# Main_Board.net
KiCad netlist of a schematic drawn in Altium Designer
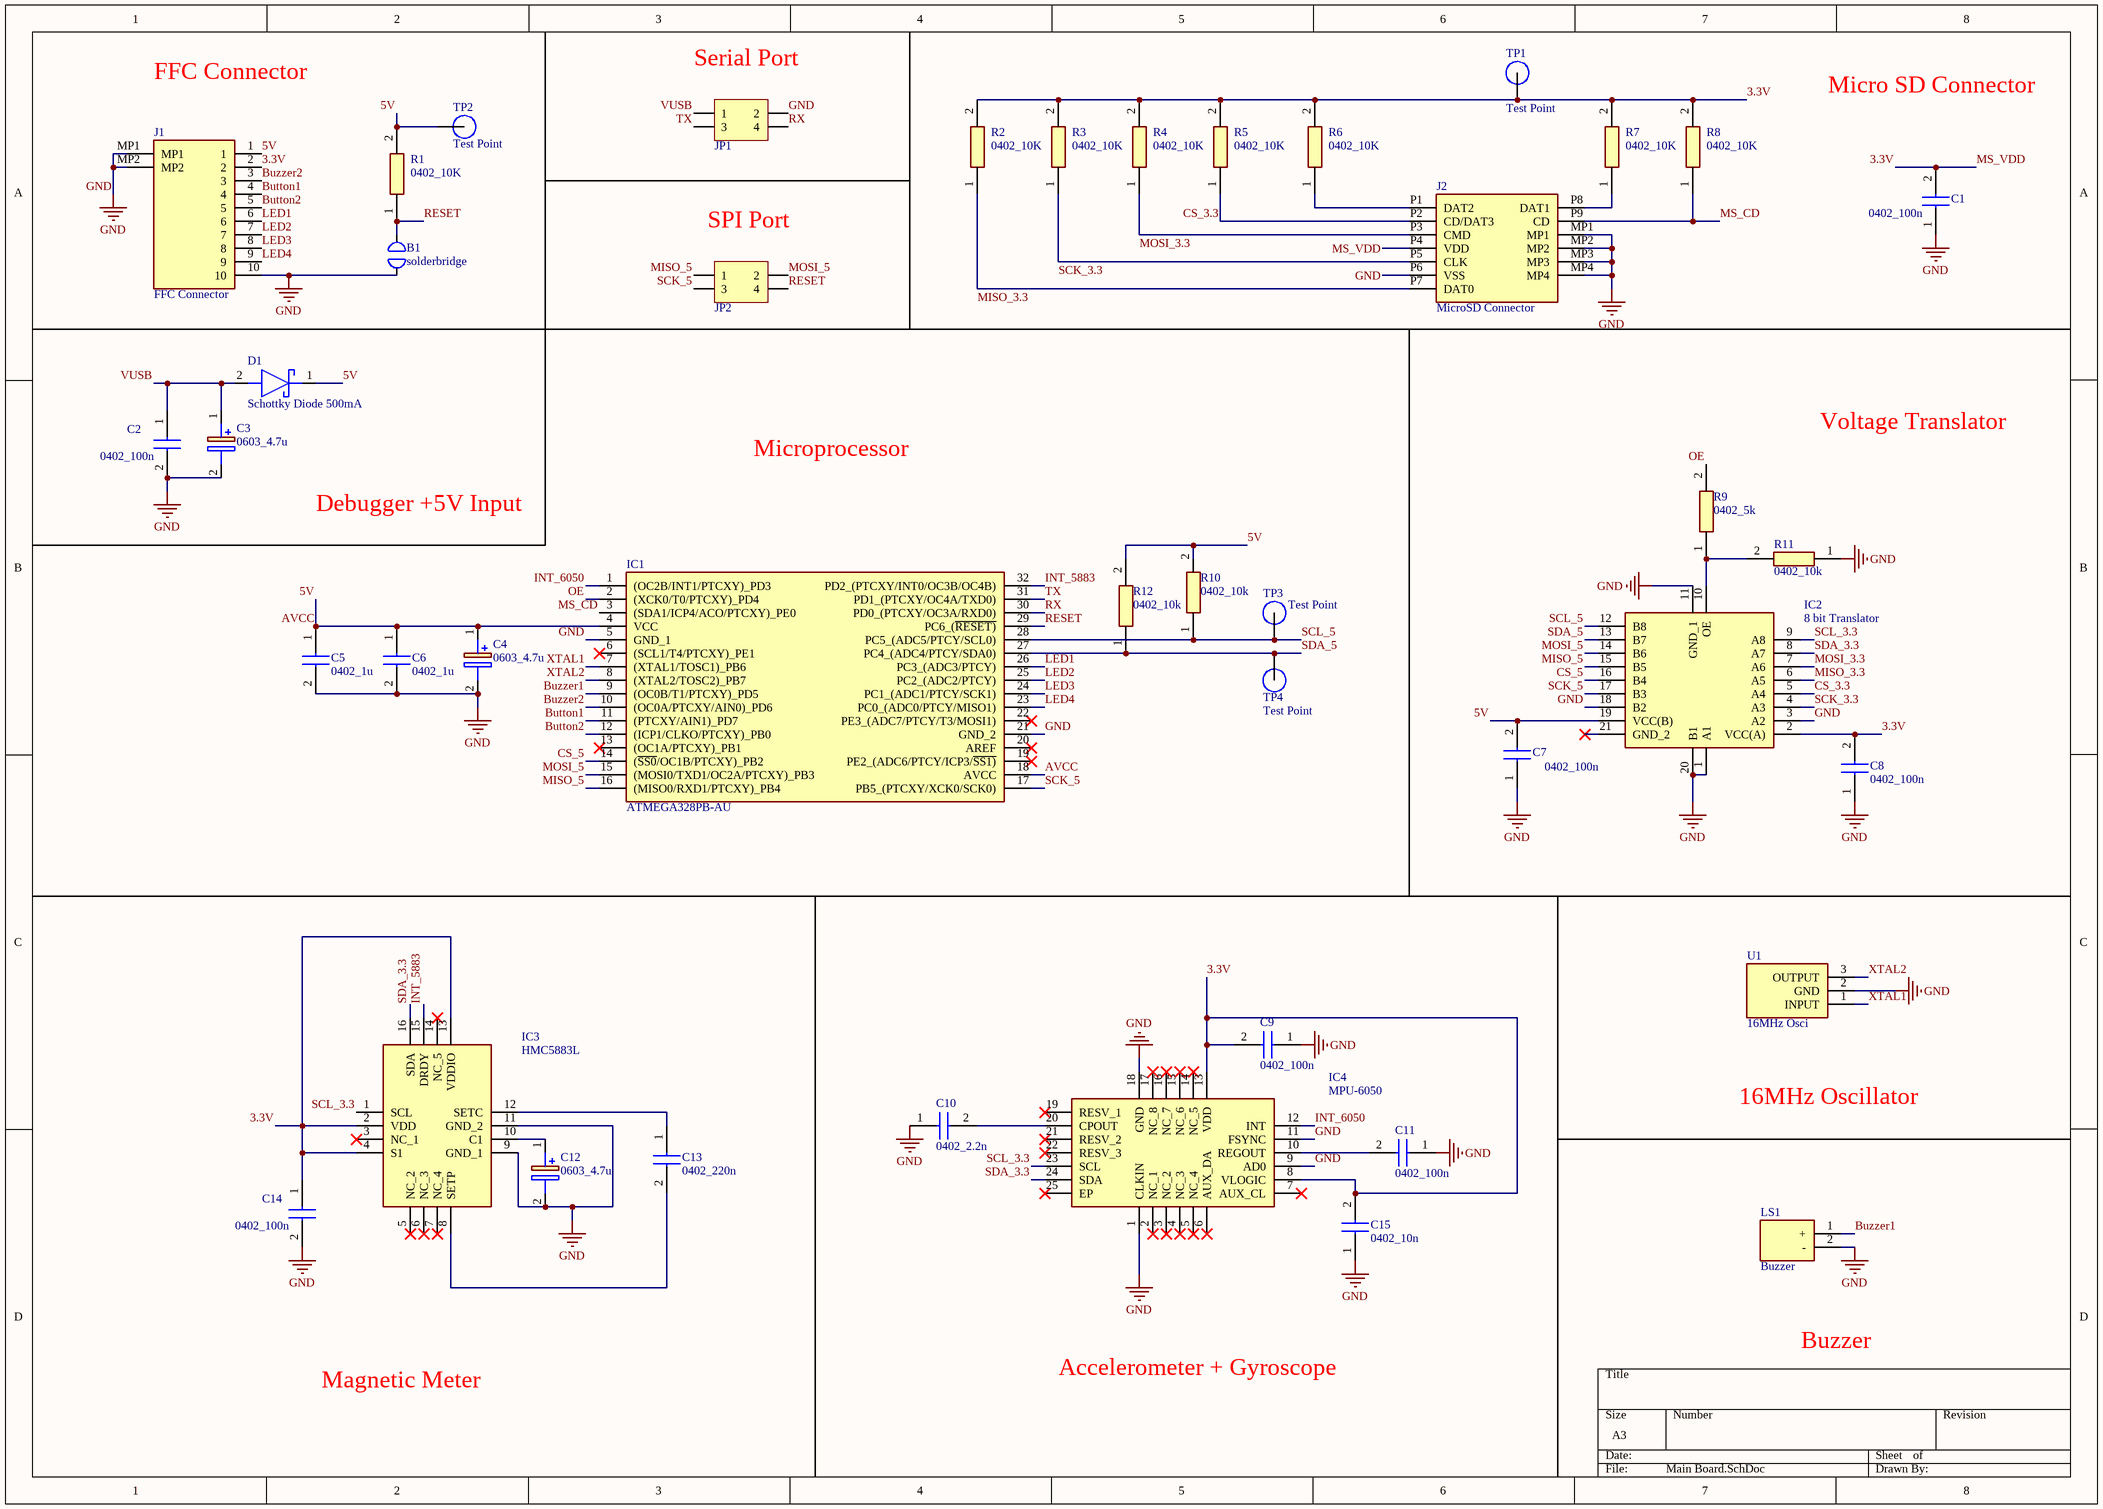
[diagram p0: Main Board.SchDoc]

(export (version "E")
  (design (tool "Eeschema 10.0.6"))
  (components
    (comp (ref "B1")
      (value "solderbridge")
      (footprint "Solderbridge")
      (libsource (lib "Main Board SCH Lib") (part "solderbridge"))
    )
    (comp (ref "C1")
      (value "0402_100n")
      (footprint "Main Board PCB Lib:CAPC1005X55N")
      (description "Capacitor")
      (fields (field (name "MANUFACTURER_PART_NUMBER") "VJ0603HIFRQ1KIT"))
      (libsource (lib "Main Board SCH Lib") (part "0603_C"))
    )
    (comp (ref "C2")
      (value "0402_100n")
      (footprint "CAPC1005X55N")
      (description "Capacitor")
      (fields (field (name "MANUFACTURER_PART_NUMBER") "VJ0603HIFRQ1KIT"))
      (libsource (lib "Main Board SCH Lib") (part "0603_C"))
    )
    (comp (ref "C3")
      (value "0603_4.7u")
      (footprint "SamacSys:CAPPM168X90N")
      (description "Capacitor Polarised")
      (fields (field (name "MANUFACTURER_PART_NUMBER") "TMCJ0J475MTRF"))
      (libsource (lib "Main Board SCH Lib") (part "0603_Tan"))
    )
    (comp (ref "C4")
      (value "0603_4.7u")
      (footprint "SamacSys:CAPPM168X90N")
      (description "Capacitor Polarised")
      (fields (field (name "MANUFACTURER_PART_NUMBER") "TMCJ0J475MTRF"))
      (libsource (lib "Main Board SCH Lib") (part "0603_Tan"))
    )
    (comp (ref "C5")
      (value "0402_1u")
      (footprint "Main Board PCB Lib:CAPC1005X55N")
      (description "Capacitor")
      (fields (field (name "MANUFACTURER_PART_NUMBER") "VJ0603HIFRQ1KIT"))
      (libsource (lib "Main Board SCH Lib") (part "0603_C"))
    )
    (comp (ref "C6")
      (value "0402_1u")
      (footprint "Main Board PCB Lib:CAPC1005X55N")
      (description "Capacitor")
      (fields (field (name "MANUFACTURER_PART_NUMBER") "VJ0603HIFRQ1KIT"))
      (libsource (lib "Main Board SCH Lib") (part "0603_C"))
    )
    (comp (ref "C7")
      (value "0402_100n")
      (footprint "Main Board PCB Lib:CAPC1005X55N")
      (description "Capacitor")
      (fields (field (name "MANUFACTURER_PART_NUMBER") "VJ0603HIFRQ1KIT"))
      (libsource (lib "Main Board SCH Lib") (part "0603_C"))
    )
    (comp (ref "C8")
      (value "0402_100n")
      (footprint "Main Board PCB Lib:CAPC1005X55N")
      (description "Capacitor")
      (fields (field (name "MANUFACTURER_PART_NUMBER") "VJ0603HIFRQ1KIT"))
      (libsource (lib "Main Board SCH Lib") (part "0603_C"))
    )
    (comp (ref "C9")
      (value "0402_100n")
      (footprint "Main Board PCB Lib:CAPC1005X55N")
      (description "Capacitor")
      (fields (field (name "MANUFACTURER_PART_NUMBER") "VJ0603HIFRQ1KIT"))
      (libsource (lib "Main Board SCH Lib") (part "0603_C"))
    )
    (comp (ref "C10")
      (value "0402_2.2n")
      (footprint "Main Board PCB Lib:CAPC1005X55N")
      (description "Capacitor")
      (fields (field (name "MANUFACTURER_PART_NUMBER") "VJ0603HIFRQ1KIT"))
      (libsource (lib "Main Board SCH Lib") (part "0603_C"))
    )
    (comp (ref "C11")
      (value "0402_100n")
      (footprint "Main Board PCB Lib:CAPC1005X55N")
      (description "Capacitor")
      (fields (field (name "MANUFACTURER_PART_NUMBER") "VJ0603HIFRQ1KIT"))
      (libsource (lib "Main Board SCH Lib") (part "0603_C"))
    )
    (comp (ref "C12")
      (value "0603_4.7u")
      (footprint "SamacSys:CAPPM168X90N")
      (description "Capacitor Polarised")
      (fields (field (name "MANUFACTURER_PART_NUMBER") "TMCJ0J475MTRF"))
      (libsource (lib "Main Board SCH Lib") (part "0603_Tan"))
    )
    (comp (ref "C13")
      (value "0402_220n")
      (footprint "Main Board PCB Lib:CAPC1005X55N")
      (description "Capacitor")
      (fields (field (name "MANUFACTURER_PART_NUMBER") "VJ0603HIFRQ1KIT"))
      (libsource (lib "Main Board SCH Lib") (part "0603_C"))
    )
    (comp (ref "C14")
      (value "0402_100n")
      (footprint "Main Board PCB Lib:CAPC1005X55N")
      (description "Capacitor")
      (fields (field (name "MANUFACTURER_PART_NUMBER") "VJ0603HIFRQ1KIT"))
      (libsource (lib "Main Board SCH Lib") (part "0603_C"))
    )
    (comp (ref "C15")
      (value "0402_10n")
      (footprint "Main Board PCB Lib:CAPC1005X55N")
      (description "Capacitor")
      (fields (field (name "MANUFACTURER_PART_NUMBER") "VJ0603HIFRQ1KIT"))
      (libsource (lib "Main Board SCH Lib") (part "0603_C"))
    )
    (comp (ref "D1")
      (value "Schottky Diode 500mA")
      (footprint "SamacSys:DIOC1709X85N")
      (description "Schottky Diode")
      (fields
        (field (name "MOUSER2 PART NUMBER") "750-CDBU0520")
        (field (name "MANUFACTURER_PART_NUMBER") "CDBU0520")
      )
      (libsource (lib "Main Board SCH Lib") (part "Schottky Diode 500mA"))
    )
    (comp (ref "IC1")
      (value "ATMEGA328PB-AU")
      (footprint "SamacSys:QFP80P900X900X120-32N")
      (description "Integrated Circuit")
      (fields (field (name "MOUSER2 PART NUMBER") "556-ATMEGA328PB-AU"))
      (libsource (lib "Main Board SCH Lib") (part "ATMEGA328PB-AU"))
    )
    (comp (ref "IC2")
      (value "8 bit Translator")
      (footprint "SamacSys:NXB0108BQX")
      (description "Integrated Circuit")
      (fields (field (name "MANUFACTURER_PART_NUMBER") "NXB0108BQX"))
      (libsource (lib "Main Board SCH Lib") (part "8 bit Translator"))
    )
    (comp (ref "IC3")
      (value "HMC5883L")
      (footprint "SamacSys:HMC5883L")
      (description "Integrated Circuit")
      (libsource (lib "Main Board SCH Lib") (part "HMC5883L"))
    )
    (comp (ref "IC4")
      (value "MPU-6050")
      (footprint "MPU_6050")
      (description "Integrated Circuit")
      (libsource (lib "Main Board SCH Lib") (part "MPU-6050"))
    )
    (comp (ref "J1")
      (value "FFC Connector")
      (footprint "SamacSys:528921033")
      (description "Connector")
      (fields (field (name "MANUFACTURER_PART_NUMBER") "52892-1033"))
      (libsource (lib "Main Board SCH Lib") (part "FFC Connector"))
    )
    (comp (ref "J2")
      (value "MicroSD Connector")
      (footprint "SamacSys:MEM20750014001A")
      (description "Connector")
      (fields (field (name "MANUFACTURER_PART_NUMBER") "MEM2075-00-140-01-A"))
      (libsource (lib "Main Board SCH Lib") (part "MEM2075-00-140-01-A"))
    )
    (comp (ref "JP1")
      (value "Header2X2")
      (footprint "HDR2.54-LI-2x2P")
      (description "Header 2X2")
      (fields (field (name "版权归属") "源创客"))
      (libsource (lib "Main Board SCH Lib") (part "Header 2X2"))
    )
    (comp (ref "JP2")
      (value "Header2X2")
      (footprint "HDR2.54-LI-2x2P")
      (description "Header 2X2")
      (fields (field (name "版权归属") "源创客"))
      (libsource (lib "Main Board SCH Lib") (part "Header 2X2"))
    )
    (comp (ref "LS1")
      (value "Buzzer")
      (footprint "SamacSys:CPT1212381SMTTR")
      (description "Loudspeaker or Buzzer")
      (fields (field (name "MANUFACTURER_PART_NUMBER") "CPT-12123-81-SMT-TR"))
      (libsource (lib "Main Board SCH Lib") (part "Buzzer"))
    )
    (comp (ref "R1")
      (value "0402_10K")
      (footprint "Main Board PCB Lib:0402_R")
      (description "Resistor")
      (fields (field (name "MANUFACTURER_PART_NUMBER") "ERA-2ARB472X"))
      (libsource (lib "Main Board SCH Lib") (part "0402_R"))
    )
    (comp (ref "R2")
      (value "0402_10K")
      (footprint "Main Board PCB Lib:0402_R")
      (description "Resistor")
      (fields (field (name "MANUFACTURER_PART_NUMBER") "ERA-2ARB472X"))
      (libsource (lib "Main Board SCH Lib") (part "0402_R"))
    )
    (comp (ref "R3")
      (value "0402_10K")
      (footprint "Main Board PCB Lib:0402_R")
      (description "Resistor")
      (fields (field (name "MANUFACTURER_PART_NUMBER") "ERA-2ARB472X"))
      (libsource (lib "Main Board SCH Lib") (part "0402_R"))
    )
    (comp (ref "R4")
      (value "0402_10K")
      (footprint "Main Board PCB Lib:0402_R")
      (description "Resistor")
      (fields (field (name "MANUFACTURER_PART_NUMBER") "ERA-2ARB472X"))
      (libsource (lib "Main Board SCH Lib") (part "0402_R"))
    )
    (comp (ref "R5")
      (value "0402_10K")
      (footprint "Main Board PCB Lib:0402_R")
      (description "Resistor")
      (fields (field (name "MANUFACTURER_PART_NUMBER") "ERA-2ARB472X"))
      (libsource (lib "Main Board SCH Lib") (part "0402_R"))
    )
    (comp (ref "R6")
      (value "0402_10K")
      (footprint "Main Board PCB Lib:0402_R")
      (description "Resistor")
      (fields (field (name "MANUFACTURER_PART_NUMBER") "ERA-2ARB472X"))
      (libsource (lib "Main Board SCH Lib") (part "0402_R"))
    )
    (comp (ref "R7")
      (value "0402_10K")
      (footprint "Main Board PCB Lib:0402_R")
      (description "Resistor")
      (fields (field (name "MANUFACTURER_PART_NUMBER") "ERA-2ARB472X"))
      (libsource (lib "Main Board SCH Lib") (part "0402_R"))
    )
    (comp (ref "R8")
      (value "0402_10K")
      (footprint "Main Board PCB Lib:0402_R")
      (description "Resistor")
      (fields (field (name "MANUFACTURER_PART_NUMBER") "ERA-2ARB472X"))
      (libsource (lib "Main Board SCH Lib") (part "0402_R"))
    )
    (comp (ref "R9")
      (value "0402_5k")
      (footprint "Main Board PCB Lib:0402_R")
      (description "Resistor")
      (fields (field (name "MANUFACTURER_PART_NUMBER") "ERA-2ARB472X"))
      (libsource (lib "Main Board SCH Lib") (part "0402_R"))
    )
    (comp (ref "R10")
      (value "0402_10k")
      (footprint "Main Board PCB Lib:0402_R")
      (description "Resistor")
      (fields (field (name "MANUFACTURER_PART_NUMBER") "ERA-2ARB472X"))
      (libsource (lib "Main Board SCH Lib") (part "0402_R"))
    )
    (comp (ref "R11")
      (value "0402_10k")
      (footprint "Main Board PCB Lib:0402_R")
      (description "Resistor")
      (fields (field (name "MANUFACTURER_PART_NUMBER") "ERA-2ARB472X"))
      (libsource (lib "") (part "0402_R_1"))
    )
    (comp (ref "R12")
      (value "0402_10k")
      (footprint "Main Board PCB Lib:0402_R")
      (description "Resistor")
      (fields (field (name "MANUFACTURER_PART_NUMBER") "ERA-2ARB472X"))
      (libsource (lib "Main Board SCH Lib") (part "0402_R"))
    )
    (comp (ref "TP1")
      (value "Test Point")
      (footprint "TP_SMD_D1.0mm")
      (libsource (lib "Main Board SCH Lib") (part "Test Point"))
    )
    (comp (ref "TP2")
      (value "Test Point")
      (footprint "TP_SMD_D1.0mm")
      (libsource (lib "Main Board SCH Lib") (part "Test Point"))
    )
    (comp (ref "TP3")
      (value "Test Point")
      (footprint "TP_SMD_D1.0mm")
      (libsource (lib "Main Board SCH Lib") (part "Test Point"))
    )
    (comp (ref "TP4")
      (value "Test Point")
      (footprint "TP_SMD_D1.0mm")
      (libsource (lib "Main Board SCH Lib") (part "Test Point"))
    )
    (comp (ref "U1")
      (value "16MHz Osci")
      (footprint "SamacSys:CSTNE16M0V530000R0")
      (description "Undefined or Miscellaneous")
      (fields
        (field (name "MOUSER2 PART NUMBER") "81-CSTNE16M0V530000R")
        (field (name "MANUFACTURER_PART_NUMBER") "CSTNE16M0V530000R0")
      )
      (libsource (lib "Main Board SCH Lib") (part "16MHz Osci"))
    )
  )
  (nets
    (net (code "1") (name "/3.3V") (class "Default")
      (node (ref "C1") (pin "2") (pinfunction "2_2") (pintype "passive"))
      (node (ref "C14") (pin "1") (pinfunction "1_1") (pintype "passive"))
      (node (ref "C15") (pin "2") (pinfunction "2_2") (pintype "passive"))
      (node (ref "C8") (pin "2") (pinfunction "2_2") (pintype "passive"))
      (node (ref "C9") (pin "2") (pinfunction "2_2") (pintype "passive"))
      (node (ref "IC2") (pin "2") (pinfunction "VCC(A)_2") (pintype "passive"))
      (node (ref "IC3") (pin "13") (pinfunction "VDDIO_13") (pintype "passive"))
      (node (ref "IC3") (pin "2") (pinfunction "VDD_2") (pintype "passive"))
      (node (ref "IC3") (pin "4") (pinfunction "S1_4") (pintype "passive"))
      (node (ref "IC4") (pin "13") (pinfunction "VDD_13") (pintype "passive"))
      (node (ref "IC4") (pin "8") (pinfunction "VLOGIC_8") (pintype "passive"))
      (node (ref "J1") (pin "2") (pinfunction "2_2") (pintype "passive"))
      (node (ref "J2") (pin "P4") (pinfunction "VDD_P4") (pintype "passive"))
      (node (ref "R2") (pin "2") (pinfunction "2_2") (pintype "passive"))
      (node (ref "R3") (pin "2") (pinfunction "2_2") (pintype "passive"))
      (node (ref "R4") (pin "2") (pinfunction "2_2") (pintype "passive"))
      (node (ref "R5") (pin "2") (pinfunction "2_2") (pintype "passive"))
      (node (ref "R6") (pin "2") (pinfunction "2_2") (pintype "passive"))
      (node (ref "R7") (pin "2") (pinfunction "2_2") (pintype "passive"))
      (node (ref "R8") (pin "2") (pinfunction "2_2") (pintype "passive"))
      (node (ref "TP1") (pin "1") (pinfunction "1_1") (pintype "passive"))
    )
    (net (code "2") (name "/5V") (class "Default")
      (node (ref "C4") (pin "1") (pinfunction "+_1") (pintype "passive"))
      (node (ref "C5") (pin "1") (pinfunction "1_1") (pintype "passive"))
      (node (ref "C6") (pin "1") (pinfunction "1_1") (pintype "passive"))
      (node (ref "C7") (pin "2") (pinfunction "2_2") (pintype "passive"))
      (node (ref "D1") (pin "1") (pinfunction "K_1") (pintype "passive"))
      (node (ref "IC1") (pin "18") (pinfunction "AVCC_18") (pintype "passive"))
      (node (ref "IC1") (pin "4") (pinfunction "VCC_4") (pintype "passive"))
      (node (ref "IC2") (pin "19") (pinfunction "VCC(B)_19") (pintype "passive"))
      (node (ref "J1") (pin "1") (pinfunction "1_1") (pintype "passive"))
      (node (ref "R1") (pin "2") (pinfunction "2_2") (pintype "passive"))
      (node (ref "R10") (pin "2") (pinfunction "2_2") (pintype "passive"))
      (node (ref "R12") (pin "2") (pinfunction "2_2") (pintype "passive"))
      (node (ref "TP2") (pin "1") (pinfunction "1_1") (pintype "passive"))
    )
    (net (code "3") (name "/Button1") (class "Default")
      (node (ref "IC1") (pin "11") (pinfunction "(PTCXY/AIN1)_PD7_11") (pintype "passive"))
      (node (ref "J1") (pin "4") (pinfunction "4_4") (pintype "passive"))
    )
    (net (code "4") (name "/Button2") (class "Default")
      (node (ref "IC1") (pin "12") (pinfunction "(ICP1/CLKO/PTCXY)_PB0_12") (pintype "passive"))
      (node (ref "J1") (pin "5") (pinfunction "5_5") (pintype "passive"))
    )
    (net (code "5") (name "/Buzzer1") (class "Default")
      (node (ref "IC1") (pin "9") (pinfunction "(OC0B/T1/PTCXY)_PD5_9") (pintype "passive"))
      (node (ref "LS1") (pin "1") (pinfunction "+_1") (pintype "passive"))
    )
    (net (code "6") (name "/Buzzer2") (class "Default")
      (node (ref "IC1") (pin "10") (pinfunction "(OC0A/PTCXY/AIN0)_PD6_10") (pintype "passive"))
      (node (ref "J1") (pin "3") (pinfunction "3_3") (pintype "passive"))
    )
    (net (code "7") (name "/CS_3.3") (class "Default")
      (node (ref "IC2") (pin "5") (pinfunction "A4_5") (pintype "passive"))
      (node (ref "J2") (pin "P2") (pinfunction "CD/DAT3_P2") (pintype "passive"))
      (node (ref "R5") (pin "1") (pinfunction "1_1") (pintype "passive"))
    )
    (net (code "8") (name "/CS_5") (class "Default")
      (node (ref "IC1") (pin "14") (pinfunction "(~{SS0}/OC1B/PTCXY)_PB2_14") (pintype "passive"))
      (node (ref "IC2") (pin "16") (pinfunction "B4_16") (pintype "passive"))
    )
    (net (code "9") (name "/INT_5883") (class "Default")
      (node (ref "IC1") (pin "32") (pinfunction "PD2_(PTCXY/INT0/OC3B/OC4B)_32") (pintype "passive"))
      (node (ref "IC3") (pin "15") (pinfunction "DRDY_15") (pintype "passive"))
    )
    (net (code "10") (name "/INT_6050") (class "Default")
      (node (ref "IC1") (pin "1") (pinfunction "(OC2B/INT1/PTCXY)_PD3_1") (pintype "passive"))
      (node (ref "IC4") (pin "12") (pinfunction "INT_12") (pintype "passive"))
    )
    (net (code "11") (name "/LED1") (class "Default")
      (node (ref "IC1") (pin "26") (pinfunction "PC3_(ADC3/PTCY)_26") (pintype "passive"))
      (node (ref "J1") (pin "6") (pinfunction "6_6") (pintype "passive"))
    )
    (net (code "12") (name "/LED2") (class "Default")
      (node (ref "IC1") (pin "25") (pinfunction "PC2_(ADC2/PTCY)_25") (pintype "passive"))
      (node (ref "J1") (pin "7") (pinfunction "7_7") (pintype "passive"))
    )
    (net (code "13") (name "/LED3") (class "Default")
      (node (ref "IC1") (pin "24") (pinfunction "PC1_(ADC1/PTCY/SCK1)_24") (pintype "passive"))
      (node (ref "J1") (pin "8") (pinfunction "8_8") (pintype "passive"))
    )
    (net (code "14") (name "/LED4") (class "Default")
      (node (ref "IC1") (pin "23") (pinfunction "PC0_(ADC0/PTCY/MISO1)_23") (pintype "passive"))
      (node (ref "J1") (pin "9") (pinfunction "9_9") (pintype "passive"))
    )
    (net (code "15") (name "/MISO_3.3") (class "Default")
      (node (ref "IC2") (pin "6") (pinfunction "A5_6") (pintype "passive"))
      (node (ref "J2") (pin "P7") (pinfunction "DAT0_P7") (pintype "passive"))
      (node (ref "R2") (pin "1") (pinfunction "1_1") (pintype "passive"))
    )
    (net (code "16") (name "/MISO_5") (class "Default")
      (node (ref "IC1") (pin "16") (pinfunction "(MISO0/RXD1/PTCXY)_PB4_16") (pintype "passive"))
      (node (ref "IC2") (pin "15") (pinfunction "B5_15") (pintype "passive"))
      (node (ref "JP2") (pin "1") (pinfunction "1_1") (pintype "passive"))
    )
    (net (code "17") (name "/MOSI_3.3") (class "Default")
      (node (ref "IC2") (pin "7") (pinfunction "A6_7") (pintype "passive"))
      (node (ref "J2") (pin "P3") (pinfunction "CMD_P3") (pintype "passive"))
      (node (ref "R4") (pin "1") (pinfunction "1_1") (pintype "passive"))
    )
    (net (code "18") (name "/MOSI_5") (class "Default")
      (node (ref "IC1") (pin "15") (pinfunction "(MOSI0/TXD1/OC2A/PTCXY)_PB3_15") (pintype "passive"))
      (node (ref "IC2") (pin "14") (pinfunction "B6_14") (pintype "passive"))
      (node (ref "JP2") (pin "2") (pinfunction "2_2") (pintype "passive"))
    )
    (net (code "19") (name "/MS_CD") (class "Default")
      (node (ref "IC1") (pin "3") (pinfunction "(SDA1/ICP4/ACO/PTCXY)_PE0_3") (pintype "passive"))
      (node (ref "J2") (pin "P9") (pinfunction "CD_P9") (pintype "passive"))
      (node (ref "R8") (pin "1") (pinfunction "1_1") (pintype "passive"))
    )
    (net (code "20") (name "/OE") (class "Default")
      (node (ref "IC1") (pin "2") (pinfunction "(XCK0/T0/PTCXY)_PD4_2") (pintype "passive"))
      (node (ref "R9") (pin "2") (pinfunction "2_2") (pintype "passive"))
    )
    (net (code "21") (name "/RESET") (class "Default")
      (node (ref "B1") (pin "1") (pinfunction "0_1") (pintype "passive"))
      (node (ref "IC1") (pin "29") (pinfunction "PC6_(~{RESET)}_29") (pintype "passive"))
      (node (ref "JP2") (pin "4") (pinfunction "4_4") (pintype "passive"))
      (node (ref "R1") (pin "1") (pinfunction "1_1") (pintype "passive"))
    )
    (net (code "22") (name "/RX") (class "Default")
      (node (ref "IC1") (pin "30") (pinfunction "PD0_(PTCXY/OC3A/RXD0)_30") (pintype "passive"))
      (node (ref "JP1") (pin "4") (pinfunction "4_4") (pintype "passive"))
    )
    (net (code "23") (name "/SCK_3.3") (class "Default")
      (node (ref "IC2") (pin "4") (pinfunction "A3_4") (pintype "passive"))
      (node (ref "J2") (pin "P5") (pinfunction "CLK_P5") (pintype "passive"))
      (node (ref "R3") (pin "1") (pinfunction "1_1") (pintype "passive"))
    )
    (net (code "24") (name "/SCK_5") (class "Default")
      (node (ref "IC1") (pin "17") (pinfunction "PB5_(PTCXY/XCK0/SCK0)_17") (pintype "passive"))
      (node (ref "IC2") (pin "17") (pinfunction "B3_17") (pintype "passive"))
      (node (ref "JP2") (pin "3") (pinfunction "3_3") (pintype "passive"))
    )
    (net (code "25") (name "/SCL_3.3") (class "Default")
      (node (ref "IC2") (pin "9") (pinfunction "A8_9") (pintype "passive"))
      (node (ref "IC3") (pin "1") (pinfunction "SCL_1") (pintype "passive"))
      (node (ref "IC4") (pin "23") (pinfunction "SCL_23") (pintype "passive"))
    )
    (net (code "26") (name "/SCL_5") (class "Default")
      (node (ref "IC1") (pin "28") (pinfunction "PC5_(ADC5/PTCY/SCL0)_28") (pintype "passive"))
      (node (ref "IC2") (pin "12") (pinfunction "B8_12") (pintype "passive"))
      (node (ref "R10") (pin "1") (pinfunction "1_1") (pintype "passive"))
      (node (ref "TP3") (pin "1") (pinfunction "1_1") (pintype "passive"))
    )
    (net (code "27") (name "/SDA_3.3") (class "Default")
      (node (ref "IC2") (pin "8") (pinfunction "A7_8") (pintype "passive"))
      (node (ref "IC3") (pin "16") (pinfunction "SDA_16") (pintype "passive"))
      (node (ref "IC4") (pin "24") (pinfunction "SDA_24") (pintype "passive"))
    )
    (net (code "28") (name "/SDA_5") (class "Default")
      (node (ref "IC1") (pin "27") (pinfunction "PC4_(ADC4/PTCY/SDA0)_27") (pintype "passive"))
      (node (ref "IC2") (pin "13") (pinfunction "B7_13") (pintype "passive"))
      (node (ref "R12") (pin "1") (pinfunction "1_1") (pintype "passive"))
      (node (ref "TP4") (pin "1") (pinfunction "1_1") (pintype "passive"))
    )
    (net (code "29") (name "/TX") (class "Default")
      (node (ref "IC1") (pin "31") (pinfunction "PD1_(PTCXY/OC4A/TXD0)_31") (pintype "passive"))
      (node (ref "JP1") (pin "3") (pinfunction "3_3") (pintype "passive"))
    )
    (net (code "30") (name "/VUSB") (class "Default")
      (node (ref "C2") (pin "1") (pinfunction "1_1") (pintype "passive"))
      (node (ref "C3") (pin "1") (pinfunction "+_1") (pintype "passive"))
      (node (ref "D1") (pin "2") (pinfunction "A_2") (pintype "passive"))
      (node (ref "JP1") (pin "1") (pinfunction "1_1") (pintype "passive"))
    )
    (net (code "31") (name "/XTAL1") (class "Default")
      (node (ref "IC1") (pin "7") (pinfunction "(XTAL1/TOSC1)_PB6_7") (pintype "passive"))
      (node (ref "U1") (pin "1") (pinfunction "INPUT_1") (pintype "passive"))
    )
    (net (code "32") (name "/XTAL2") (class "Default")
      (node (ref "IC1") (pin "8") (pinfunction "(XTAL2/TOSC2)_PB7_8") (pintype "passive"))
      (node (ref "U1") (pin "3") (pinfunction "OUTPUT_3") (pintype "passive"))
    )
    (net (code "33") (name "GND") (class "Default")
      (node (ref "B1") (pin "2") (pinfunction "1_2") (pintype "passive"))
      (node (ref "C1") (pin "1") (pinfunction "1_1") (pintype "passive"))
      (node (ref "C10") (pin "1") (pinfunction "1_1") (pintype "passive"))
      (node (ref "C11") (pin "1") (pinfunction "1_1") (pintype "passive"))
      (node (ref "C12") (pin "2") (pinfunction "-_2") (pintype "passive"))
      (node (ref "C14") (pin "2") (pinfunction "2_2") (pintype "passive"))
      (node (ref "C15") (pin "1") (pinfunction "1_1") (pintype "passive"))
      (node (ref "C2") (pin "2") (pinfunction "2_2") (pintype "passive"))
      (node (ref "C3") (pin "2") (pinfunction "-_2") (pintype "passive"))
      (node (ref "C4") (pin "2") (pinfunction "-_2") (pintype "passive"))
      (node (ref "C5") (pin "2") (pinfunction "2_2") (pintype "passive"))
      (node (ref "C6") (pin "2") (pinfunction "2_2") (pintype "passive"))
      (node (ref "C7") (pin "1") (pinfunction "1_1") (pintype "passive"))
      (node (ref "C8") (pin "1") (pinfunction "1_1") (pintype "passive"))
      (node (ref "C9") (pin "1") (pinfunction "1_1") (pintype "passive"))
      (node (ref "IC1") (pin "21") (pinfunction "GND_2_21") (pintype "passive"))
      (node (ref "IC1") (pin "5") (pinfunction "GND_1_5") (pintype "passive"))
      (node (ref "IC2") (pin "1") (pinfunction "A1_1") (pintype "passive"))
      (node (ref "IC2") (pin "11") (pinfunction "GND_1_11") (pintype "passive"))
      (node (ref "IC2") (pin "18") (pinfunction "B2_18") (pintype "passive"))
      (node (ref "IC2") (pin "20") (pinfunction "B1_20") (pintype "passive"))
      (node (ref "IC2") (pin "3") (pinfunction "A2_3") (pintype "passive"))
      (node (ref "IC3") (pin "11") (pinfunction "GND_2_11") (pintype "passive"))
      (node (ref "IC3") (pin "9") (pinfunction "GND_1_9") (pintype "passive"))
      (node (ref "IC4") (pin "1") (pinfunction "CLKIN_1") (pintype "passive"))
      (node (ref "IC4") (pin "11") (pinfunction "FSYNC_11") (pintype "passive"))
      (node (ref "IC4") (pin "18") (pinfunction "GND_18") (pintype "passive"))
      (node (ref "IC4") (pin "9") (pinfunction "AD0_9") (pintype "passive"))
      (node (ref "J1") (pin "10") (pinfunction "10_10") (pintype "passive"))
      (node (ref "J1") (pin "MP1") (pinfunction "MP1_MP1") (pintype "passive"))
      (node (ref "J1") (pin "MP2") (pinfunction "MP2_MP2") (pintype "passive"))
      (node (ref "J2") (pin "MP1") (pinfunction "MP1_MP1") (pintype "passive"))
      (node (ref "J2") (pin "MP2") (pinfunction "MP2_MP2") (pintype "passive"))
      (node (ref "J2") (pin "MP3") (pinfunction "MP3_MP3") (pintype "passive"))
      (node (ref "J2") (pin "MP4") (pinfunction "MP4_MP4") (pintype "passive"))
      (node (ref "J2") (pin "P6") (pinfunction "VSS_P6") (pintype "passive"))
      (node (ref "JP1") (pin "2") (pinfunction "2_2") (pintype "passive"))
      (node (ref "LS1") (pin "2") (pinfunction "-_2") (pintype "passive"))
      (node (ref "R11") (pin "1") (pinfunction "1_1") (pintype "passive"))
      (node (ref "U1") (pin "2") (pinfunction "GND_2") (pintype "passive"))
    )
    (net (code "34") (name "Net-(C12-+)") (class "Default")
      (node (ref "C12") (pin "1") (pinfunction "+_1") (pintype "passive"))
      (node (ref "IC3") (pin "10") (pinfunction "C1_10") (pintype "passive"))
    )
    (net (code "35") (name "Net-(IC2-OE)") (class "Default")
      (node (ref "IC2") (pin "10") (pinfunction "OE_10") (pintype "passive"))
      (node (ref "R11") (pin "2") (pinfunction "2_2") (pintype "passive"))
      (node (ref "R9") (pin "1") (pinfunction "1_1") (pintype "passive"))
    )
    (net (code "36") (name "Net-(IC3-SETC)") (class "Default")
      (node (ref "C13") (pin "1") (pinfunction "1_1") (pintype "passive"))
      (node (ref "IC3") (pin "12") (pinfunction "SETC_12") (pintype "passive"))
    )
    (net (code "37") (name "Net-(IC3-SETP)") (class "Default")
      (node (ref "C13") (pin "2") (pinfunction "2_2") (pintype "passive"))
      (node (ref "IC3") (pin "8") (pinfunction "SETP_8") (pintype "passive"))
    )
    (net (code "38") (name "Net-(IC4-CPOUT)") (class "Default")
      (node (ref "C10") (pin "2") (pinfunction "2_2") (pintype "passive"))
      (node (ref "IC4") (pin "20") (pinfunction "CPOUT_20") (pintype "passive"))
    )
    (net (code "39") (name "Net-(IC4-REGOUT)") (class "Default")
      (node (ref "C11") (pin "2") (pinfunction "2_2") (pintype "passive"))
      (node (ref "IC4") (pin "10") (pinfunction "REGOUT_10") (pintype "passive"))
    )
    (net (code "40") (name "Net-(J2-DAT1)") (class "Default")
      (node (ref "J2") (pin "P8") (pinfunction "DAT1_P8") (pintype "passive"))
      (node (ref "R7") (pin "1") (pinfunction "1_1") (pintype "passive"))
    )
    (net (code "41") (name "Net-(J2-DAT2)") (class "Default")
      (node (ref "J2") (pin "P1") (pinfunction "DAT2_P1") (pintype "passive"))
      (node (ref "R6") (pin "1") (pinfunction "1_1") (pintype "passive"))
    )
    (net (code "42") (name "unconnected-(IC1-(OC1A{slash}PTCXY)_PB1-Pad13)") (class "Default")
      (node (ref "IC1") (pin "13") (pinfunction "(OC1A/PTCXY)_PB1_13") (pintype "passive+no_connect"))
    )
    (net (code "43") (name "unconnected-(IC1-(SCL1{slash}T4{slash}PTCXY)_PE1-Pad6)") (class "Default")
      (node (ref "IC1") (pin "6") (pinfunction "(SCL1/T4/PTCXY)_PE1_6") (pintype "passive+no_connect"))
    )
    (net (code "44") (name "unconnected-(IC1-AREF-Pad20)") (class "Default")
      (node (ref "IC1") (pin "20") (pinfunction "AREF_20") (pintype "passive+no_connect"))
    )
    (net (code "45") (name "unconnected-(IC1-PE2_(ADC6{slash}PTCY{slash}ICP3{slash}~{SS1)}-Pad19)") (class "Default")
      (node (ref "IC1") (pin "19") (pinfunction "PE2_(ADC6/PTCY/ICP3/~{SS1)}_19") (pintype "passive+no_connect"))
    )
    (net (code "46") (name "unconnected-(IC1-PE3_(ADC7{slash}PTCY{slash}T3{slash}MOSI1)-Pad22)") (class "Default")
      (node (ref "IC1") (pin "22") (pinfunction "PE3_(ADC7/PTCY/T3/MOSI1)_22") (pintype "passive+no_connect"))
    )
    (net (code "47") (name "unconnected-(IC2-GND_2-Pad21)") (class "Default")
      (node (ref "IC2") (pin "21") (pinfunction "GND_2_21") (pintype "passive+no_connect"))
    )
    (net (code "48") (name "unconnected-(IC3-NC_1-Pad3)") (class "Default")
      (node (ref "IC3") (pin "3") (pinfunction "NC_1_3") (pintype "passive+no_connect"))
    )
    (net (code "49") (name "unconnected-(IC3-NC_2-Pad5)") (class "Default")
      (node (ref "IC3") (pin "5") (pinfunction "NC_2_5") (pintype "passive+no_connect"))
    )
    (net (code "50") (name "unconnected-(IC3-NC_3-Pad6)") (class "Default")
      (node (ref "IC3") (pin "6") (pinfunction "NC_3_6") (pintype "passive+no_connect"))
    )
    (net (code "51") (name "unconnected-(IC3-NC_4-Pad7)") (class "Default")
      (node (ref "IC3") (pin "7") (pinfunction "NC_4_7") (pintype "passive+no_connect"))
    )
    (net (code "52") (name "unconnected-(IC3-NC_5-Pad14)") (class "Default")
      (node (ref "IC3") (pin "14") (pinfunction "NC_5_14") (pintype "passive+no_connect"))
    )
    (net (code "53") (name "unconnected-(IC4-AUX_CL-Pad7)") (class "Default")
      (node (ref "IC4") (pin "7") (pinfunction "AUX_CL_7") (pintype "passive+no_connect"))
    )
    (net (code "54") (name "unconnected-(IC4-AUX_DA-Pad6)") (class "Default")
      (node (ref "IC4") (pin "6") (pinfunction "AUX_DA_6") (pintype "passive+no_connect"))
    )
    (net (code "55") (name "unconnected-(IC4-EP-Pad25)") (class "Default")
      (node (ref "IC4") (pin "25") (pinfunction "EP_25") (pintype "passive+no_connect"))
    )
    (net (code "56") (name "unconnected-(IC4-NC_1-Pad2)") (class "Default")
      (node (ref "IC4") (pin "2") (pinfunction "NC_1_2") (pintype "passive+no_connect"))
    )
    (net (code "57") (name "unconnected-(IC4-NC_2-Pad3)") (class "Default")
      (node (ref "IC4") (pin "3") (pinfunction "NC_2_3") (pintype "passive+no_connect"))
    )
    (net (code "58") (name "unconnected-(IC4-NC_3-Pad4)") (class "Default")
      (node (ref "IC4") (pin "4") (pinfunction "NC_3_4") (pintype "passive+no_connect"))
    )
    (net (code "59") (name "unconnected-(IC4-NC_4-Pad5)") (class "Default")
      (node (ref "IC4") (pin "5") (pinfunction "NC_4_5") (pintype "passive+no_connect"))
    )
    (net (code "60") (name "unconnected-(IC4-NC_5-Pad14)") (class "Default")
      (node (ref "IC4") (pin "14") (pinfunction "NC_5_14") (pintype "passive+no_connect"))
    )
    (net (code "61") (name "unconnected-(IC4-NC_6-Pad15)") (class "Default")
      (node (ref "IC4") (pin "15") (pinfunction "NC_6_15") (pintype "passive+no_connect"))
    )
    (net (code "62") (name "unconnected-(IC4-NC_7-Pad16)") (class "Default")
      (node (ref "IC4") (pin "16") (pinfunction "NC_7_16") (pintype "passive+no_connect"))
    )
    (net (code "63") (name "unconnected-(IC4-NC_8-Pad17)") (class "Default")
      (node (ref "IC4") (pin "17") (pinfunction "NC_8_17") (pintype "passive+no_connect"))
    )
    (net (code "64") (name "unconnected-(IC4-RESV_1-Pad19)") (class "Default")
      (node (ref "IC4") (pin "19") (pinfunction "RESV_1_19") (pintype "passive+no_connect"))
    )
    (net (code "65") (name "unconnected-(IC4-RESV_2-Pad21)") (class "Default")
      (node (ref "IC4") (pin "21") (pinfunction "RESV_2_21") (pintype "passive+no_connect"))
    )
    (net (code "66") (name "unconnected-(IC4-RESV_3-Pad22)") (class "Default")
      (node (ref "IC4") (pin "22") (pinfunction "RESV_3_22") (pintype "passive+no_connect"))
    )
  )
)
